# DimmerRGB_RevB.net
KiCad netlist of a schematic drawn in EAGLE
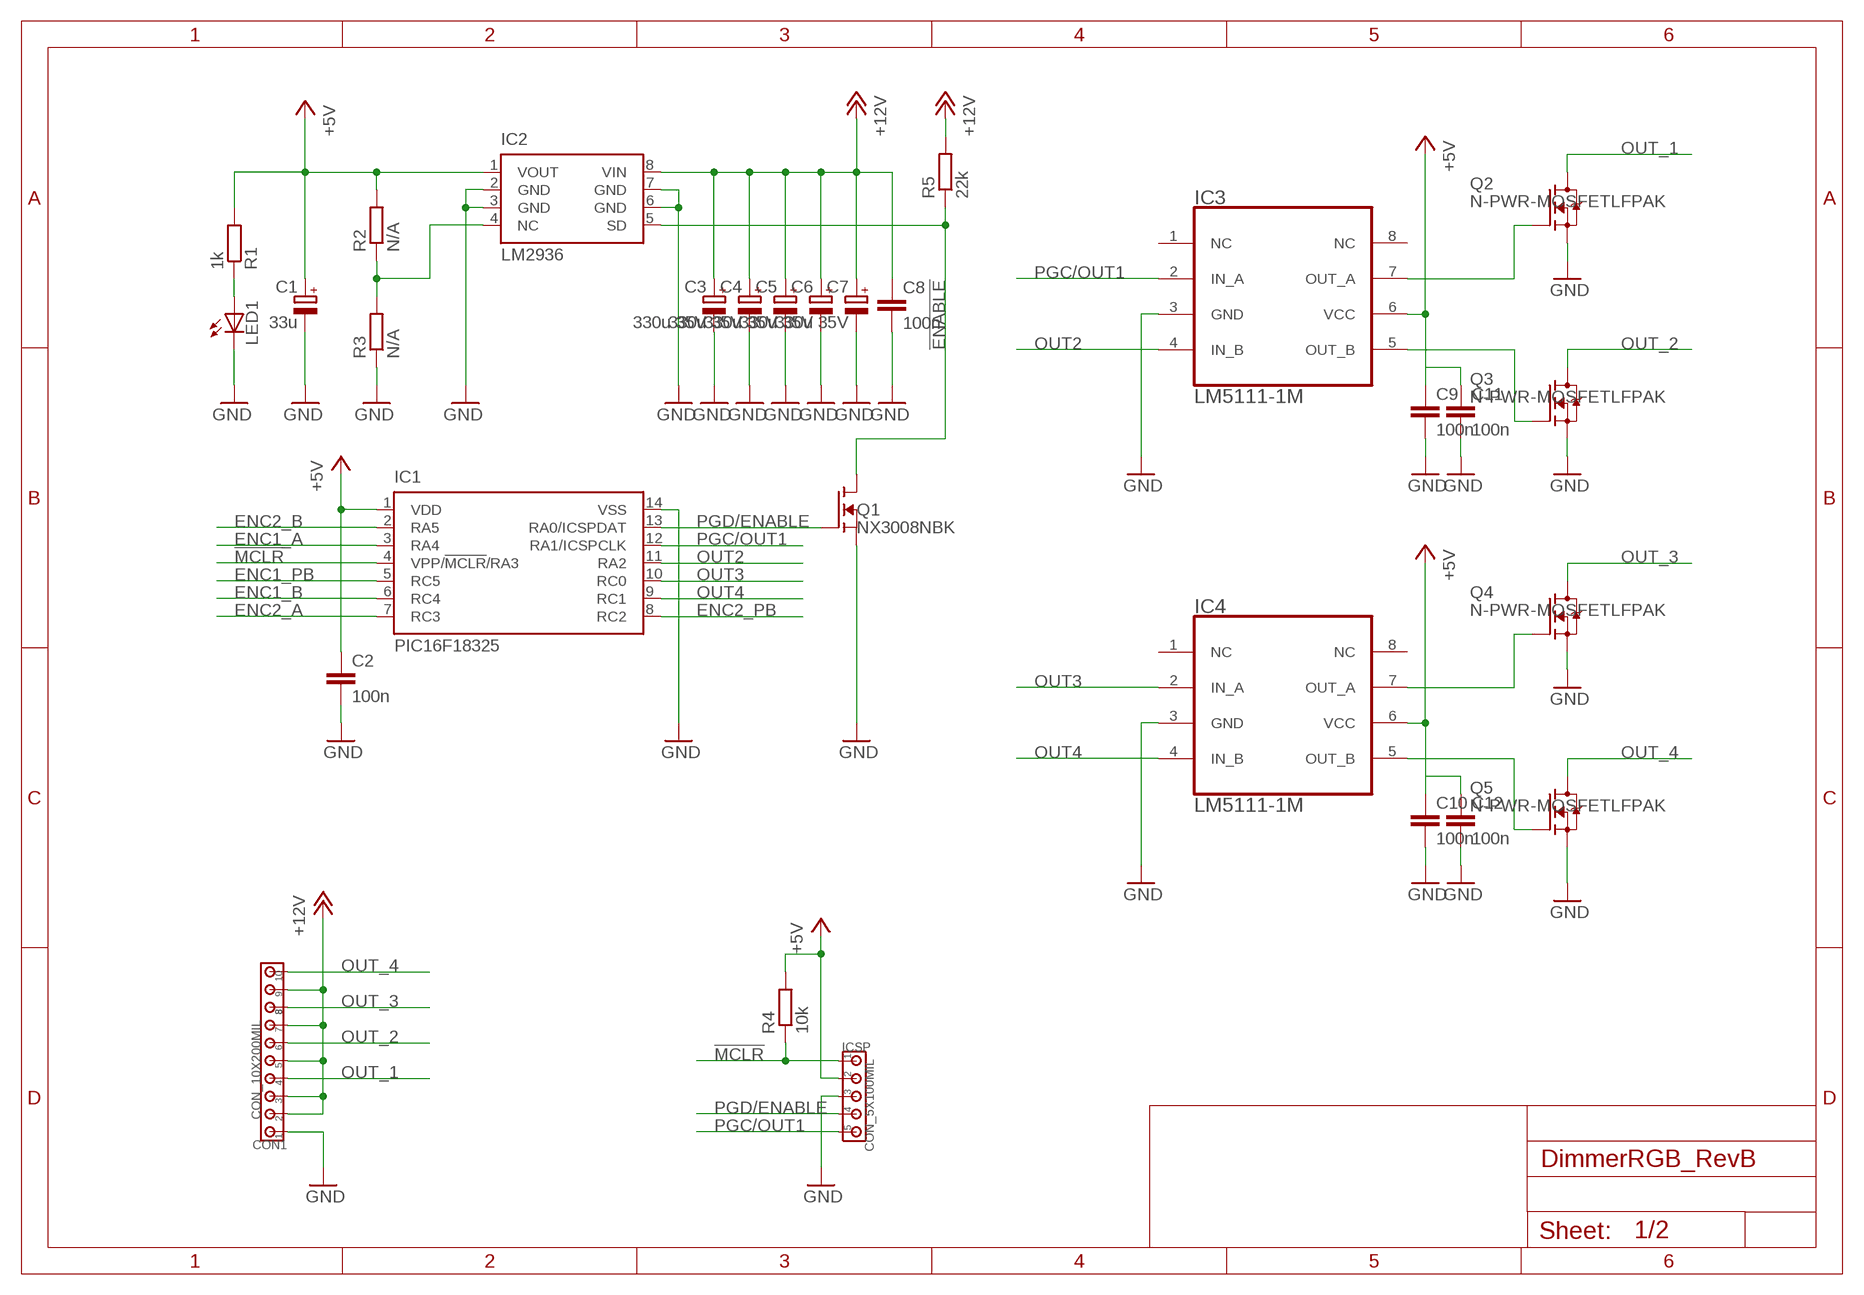
[diagram p0: schematic, sheet 1]
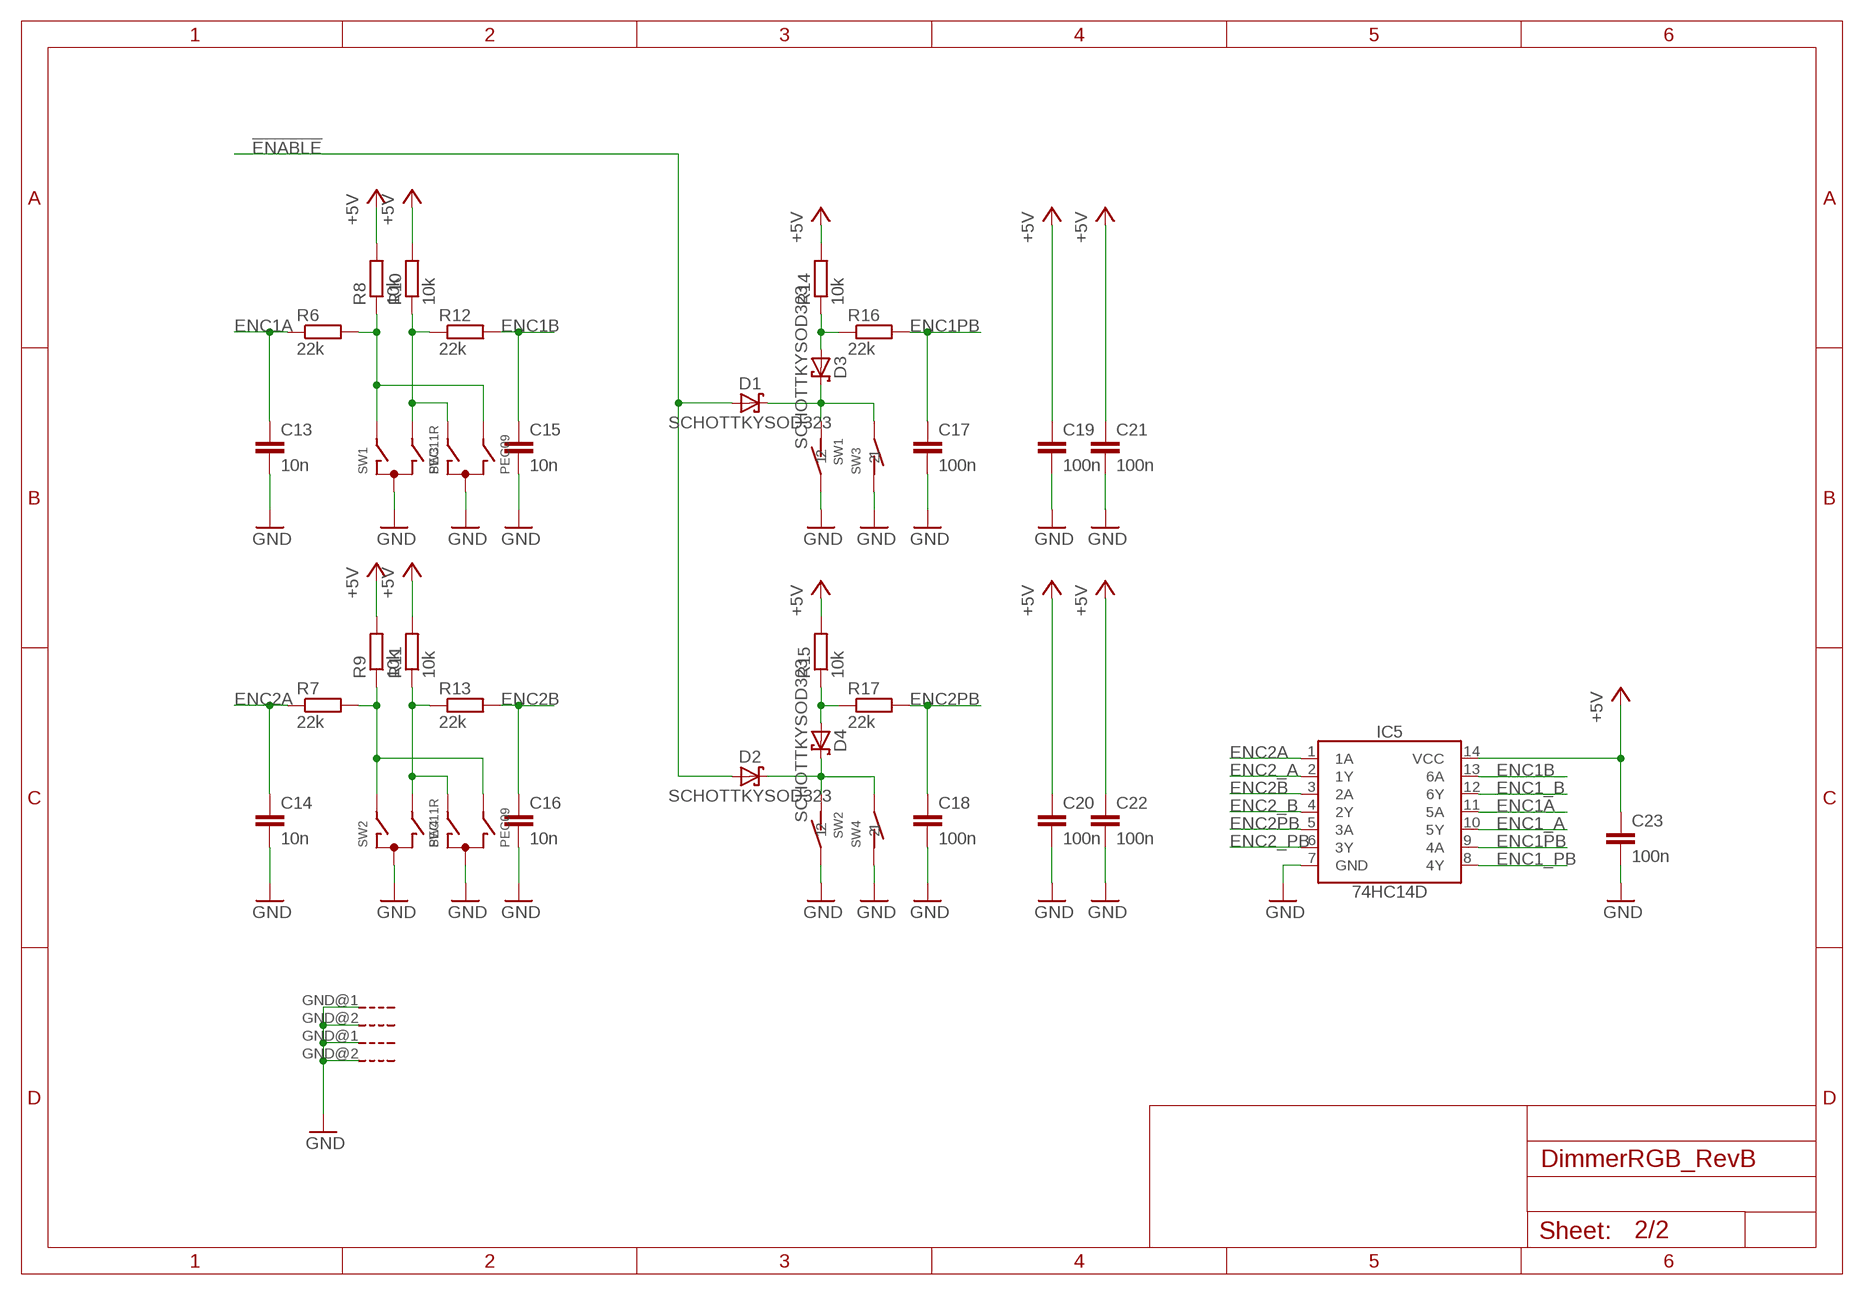
[diagram p1: schematic, sheet 2]

(export (version "E")
  (design (tool "Eeschema 10.0.6"))
  (components
    (comp (ref "C1")
      (value "33u")
      (footprint "eagle-import:SMC_C")
      (libsource (lib "eagle-import") (part "C_POLARIZEDSMC_C"))
    )
    (comp (ref "C2")
      (value "100n")
      (footprint "eagle-import:C0805")
      (libsource (lib "eagle-import") (part "CC0805"))
    )
    (comp (ref "C3")
      (value "330u 35V")
      (footprint "eagle-import:10MM")
      (libsource (lib "eagle-import") (part "C_POLARIZED10MM"))
    )
    (comp (ref "C4")
      (value "330u 35V")
      (footprint "eagle-import:10MM")
      (libsource (lib "eagle-import") (part "C_POLARIZED10MM"))
    )
    (comp (ref "C5")
      (value "330u 35V")
      (footprint "eagle-import:10MM")
      (libsource (lib "eagle-import") (part "C_POLARIZED10MM"))
    )
    (comp (ref "C6")
      (value "330u 35V")
      (footprint "eagle-import:10MM")
      (libsource (lib "eagle-import") (part "C_POLARIZED10MM"))
    )
    (comp (ref "C7")
      (value "330u 35V")
      (footprint "eagle-import:10MM")
      (libsource (lib "eagle-import") (part "C_POLARIZED10MM"))
    )
    (comp (ref "C8")
      (value "100n")
      (footprint "eagle-import:C0805")
      (libsource (lib "eagle-import") (part "CC0805"))
    )
    (comp (ref "C9")
      (value "100n")
      (footprint "eagle-import:C0805")
      (libsource (lib "eagle-import") (part "CC0805"))
    )
    (comp (ref "C10")
      (value "100n")
      (footprint "eagle-import:C0805")
      (libsource (lib "eagle-import") (part "CC0805"))
    )
    (comp (ref "C11")
      (value "100n")
      (footprint "eagle-import:C0805")
      (libsource (lib "eagle-import") (part "CC0805"))
    )
    (comp (ref "C12")
      (value "100n")
      (footprint "eagle-import:C0805")
      (libsource (lib "eagle-import") (part "CC0805"))
    )
    (comp (ref "CON1")
      (value "CON_10X200MIL")
      (footprint "eagle-import:200MIL_10X")
      (libsource (lib "eagle-import") (part "CON_10X200MIL"))
    )
    (comp (ref "IC1")
      (value "PIC16F18325")
      (footprint "eagle-import:SO14")
      (libsource (lib "eagle-import") (part "PIC16F18325"))
    )
    (comp (ref "IC2")
      (value "LM2936")
      (footprint "eagle-import:SOIC8")
      (libsource (lib "eagle-import") (part "LM2936"))
    )
    (comp (ref "IC3")
      (value "LM5111-1M")
      (footprint "eagle-import:SOIC8")
      (libsource (lib "eagle-import") (part "LM5111"))
    )
    (comp (ref "IC4")
      (value "LM5111-1M")
      (footprint "eagle-import:SOIC8")
      (libsource (lib "eagle-import") (part "LM5111"))
    )
    (comp (ref "ICSP")
      (value "CON_5X100MIL")
      (footprint "eagle-import:100MIL_5X")
      (libsource (lib "eagle-import") (part "CON_5X100MIL"))
    )
    (comp (ref "LED1")
      (value "LED0805")
      (footprint "eagle-import:LED0805")
      (libsource (lib "eagle-import") (part "LED0805"))
    )
    (comp (ref "Q1")
      (value "NX3008NBK")
      (footprint "eagle-import:SOT23")
      (libsource (lib "eagle-import") (part "N-FETSOT23"))
    )
    (comp (ref "Q2")
      (value "N-PWR-MOSFETLFPAK")
      (footprint "eagle-import:LFPAK")
      (libsource (lib "eagle-import") (part "N-PWR-MOSFETLFPAK"))
    )
    (comp (ref "Q3")
      (value "N-PWR-MOSFETLFPAK")
      (footprint "eagle-import:LFPAK")
      (libsource (lib "eagle-import") (part "N-PWR-MOSFETLFPAK"))
    )
    (comp (ref "Q4")
      (value "N-PWR-MOSFETLFPAK")
      (footprint "eagle-import:LFPAK")
      (libsource (lib "eagle-import") (part "N-PWR-MOSFETLFPAK"))
    )
    (comp (ref "Q5")
      (value "N-PWR-MOSFETLFPAK")
      (footprint "eagle-import:LFPAK")
      (libsource (lib "eagle-import") (part "N-PWR-MOSFETLFPAK"))
    )
    (comp (ref "R1")
      (value "1k")
      (footprint "eagle-import:R0805")
      (libsource (lib "eagle-import") (part "RESISTORR0805"))
    )
    (comp (ref "R2")
      (value "N/A")
      (footprint "eagle-import:R0805")
      (libsource (lib "eagle-import") (part "RESISTORR0805"))
    )
    (comp (ref "R3")
      (value "N/A")
      (footprint "eagle-import:R0805")
      (libsource (lib "eagle-import") (part "RESISTORR0805"))
    )
    (comp (ref "R4")
      (value "10k")
      (footprint "eagle-import:R0805")
      (libsource (lib "eagle-import") (part "RESISTORR0805"))
    )
    (comp (ref "R5")
      (value "22k")
      (footprint "eagle-import:R0805")
      (libsource (lib "eagle-import") (part "RESISTORR0805"))
    )
    (comp (ref "C13")
      (value "10n")
      (footprint "eagle-import:C0805")
      (libsource (lib "eagle-import") (part "CC0805"))
    )
    (comp (ref "C14")
      (value "10n")
      (footprint "eagle-import:C0805")
      (libsource (lib "eagle-import") (part "CC0805"))
    )
    (comp (ref "C15")
      (value "10n")
      (footprint "eagle-import:C0805")
      (libsource (lib "eagle-import") (part "CC0805"))
    )
    (comp (ref "C16")
      (value "10n")
      (footprint "eagle-import:C0805")
      (libsource (lib "eagle-import") (part "CC0805"))
    )
    (comp (ref "C17")
      (value "100n")
      (footprint "eagle-import:C0805")
      (libsource (lib "eagle-import") (part "CC0805"))
    )
    (comp (ref "C18")
      (value "100n")
      (footprint "eagle-import:C0805")
      (libsource (lib "eagle-import") (part "CC0805"))
    )
    (comp (ref "C19")
      (value "100n")
      (footprint "eagle-import:C0805")
      (libsource (lib "eagle-import") (part "CC0805"))
    )
    (comp (ref "C20")
      (value "100n")
      (footprint "eagle-import:C0805")
      (libsource (lib "eagle-import") (part "CC0805"))
    )
    (comp (ref "C21")
      (value "100n")
      (footprint "eagle-import:C0805")
      (libsource (lib "eagle-import") (part "CC0805"))
    )
    (comp (ref "C22")
      (value "100n")
      (footprint "eagle-import:C0805")
      (libsource (lib "eagle-import") (part "CC0805"))
    )
    (comp (ref "C23")
      (value "100n")
      (footprint "eagle-import:C0805")
      (libsource (lib "eagle-import") (part "CC0805"))
    )
    (comp (ref "D1")
      (value "SCHOTTKYSOD323")
      (footprint "eagle-import:SOD323")
      (libsource (lib "eagle-import") (part "SCHOTTKYSOD323"))
    )
    (comp (ref "D2")
      (value "SCHOTTKYSOD323")
      (footprint "eagle-import:SOD323")
      (libsource (lib "eagle-import") (part "SCHOTTKYSOD323"))
    )
    (comp (ref "D3")
      (value "SCHOTTKYSOD323")
      (footprint "eagle-import:SOD323")
      (libsource (lib "eagle-import") (part "SCHOTTKYSOD323"))
    )
    (comp (ref "D4")
      (value "SCHOTTKYSOD323")
      (footprint "eagle-import:SOD323")
      (libsource (lib "eagle-import") (part "SCHOTTKYSOD323"))
    )
    (comp (ref "IC5")
      (value "74HC14D")
      (footprint "eagle-import:SO14")
      (libsource (lib "eagle-import") (part "74HC14D"))
    )
    (comp (ref "R6")
      (value "22k")
      (footprint "eagle-import:R0805")
      (libsource (lib "eagle-import") (part "RESISTORR0805"))
    )
    (comp (ref "R7")
      (value "22k")
      (footprint "eagle-import:R0805")
      (libsource (lib "eagle-import") (part "RESISTORR0805"))
    )
    (comp (ref "R8")
      (value "10k")
      (footprint "eagle-import:R0805")
      (libsource (lib "eagle-import") (part "RESISTORR0805"))
    )
    (comp (ref "R9")
      (value "10k")
      (footprint "eagle-import:R0805")
      (libsource (lib "eagle-import") (part "RESISTORR0805"))
    )
    (comp (ref "R10")
      (value "10k")
      (footprint "eagle-import:R0805")
      (libsource (lib "eagle-import") (part "RESISTORR0805"))
    )
    (comp (ref "R11")
      (value "10k")
      (footprint "eagle-import:R0805")
      (libsource (lib "eagle-import") (part "RESISTORR0805"))
    )
    (comp (ref "R12")
      (value "22k")
      (footprint "eagle-import:R0805")
      (libsource (lib "eagle-import") (part "RESISTORR0805"))
    )
    (comp (ref "R13")
      (value "22k")
      (footprint "eagle-import:R0805")
      (libsource (lib "eagle-import") (part "RESISTORR0805"))
    )
    (comp (ref "R14")
      (value "10k")
      (footprint "eagle-import:R0805")
      (libsource (lib "eagle-import") (part "RESISTORR0805"))
    )
    (comp (ref "R15")
      (value "10k")
      (footprint "eagle-import:R0805")
      (libsource (lib "eagle-import") (part "RESISTORR0805"))
    )
    (comp (ref "R16")
      (value "22k")
      (footprint "eagle-import:R0805")
      (libsource (lib "eagle-import") (part "RESISTORR0805"))
    )
    (comp (ref "R17")
      (value "22k")
      (footprint "eagle-import:R0805")
      (libsource (lib "eagle-import") (part "RESISTORR0805"))
    )
    (comp (ref "SW1")
      (value "PEC11R")
      (footprint "eagle-import:ENCODER_BOURNS")
      (libsource (lib "eagle-import") (part "ENCODER_BOURNS"))
    )
    (comp (ref "SW2")
      (value "PEC11R")
      (footprint "eagle-import:ENCODER_BOURNS")
      (libsource (lib "eagle-import") (part "ENCODER_BOURNS"))
    )
    (comp (ref "SW3")
      (value "PEC09")
      (footprint "eagle-import:PEC09")
      (libsource (lib "eagle-import") (part "PEC09"))
    )
    (comp (ref "SW4")
      (value "PEC09")
      (footprint "eagle-import:PEC09")
      (libsource (lib "eagle-import") (part "PEC09"))
    )
  )
  (nets
    (net (code "1") (name "+5V") (class "Default")
      (node (ref "C1") (pin "+") (pinfunction "+_+") (pintype "passive"))
      (node (ref "C10") (pin "1") (pinfunction "1_1") (pintype "passive"))
      (node (ref "C11") (pin "1") (pinfunction "1_1") (pintype "passive"))
      (node (ref "C12") (pin "1") (pinfunction "1_1") (pintype "passive"))
      (node (ref "C19") (pin "1") (pinfunction "1_1") (pintype "passive"))
      (node (ref "C2") (pin "1") (pinfunction "1_1") (pintype "passive"))
      (node (ref "C20") (pin "1") (pinfunction "1_1") (pintype "passive"))
      (node (ref "C21") (pin "1") (pinfunction "1_1") (pintype "passive"))
      (node (ref "C22") (pin "1") (pinfunction "1_1") (pintype "passive"))
      (node (ref "C23") (pin "1") (pinfunction "1_1") (pintype "passive"))
      (node (ref "C9") (pin "1") (pinfunction "1_1") (pintype "passive"))
      (node (ref "IC1") (pin "1") (pinfunction "VDD_1") (pintype "power_in"))
      (node (ref "IC2") (pin "1") (pinfunction "VOUT_1") (pintype "output"))
      (node (ref "IC3") (pin "6") (pinfunction "VCC_6") (pintype "input"))
      (node (ref "IC4") (pin "6") (pinfunction "VCC_6") (pintype "input"))
      (node (ref "IC5") (pin "14") (pinfunction "VCC_14") (pintype "power_in"))
      (node (ref "ICSP") (pin "2") (pinfunction "2_2") (pintype "passive"))
      (node (ref "R1") (pin "2") (pinfunction "2_2") (pintype "passive"))
      (node (ref "R10") (pin "2") (pinfunction "2_2") (pintype "passive"))
      (node (ref "R11") (pin "2") (pinfunction "2_2") (pintype "passive"))
      (node (ref "R14") (pin "2") (pinfunction "2_2") (pintype "passive"))
      (node (ref "R15") (pin "2") (pinfunction "2_2") (pintype "passive"))
      (node (ref "R2") (pin "2") (pinfunction "2_2") (pintype "passive"))
      (node (ref "R4") (pin "2") (pinfunction "2_2") (pintype "passive"))
      (node (ref "R8") (pin "2") (pinfunction "2_2") (pintype "passive"))
      (node (ref "R9") (pin "2") (pinfunction "2_2") (pintype "passive"))
    )
    (net (code "2") (name "+12V") (class "Default")
      (node (ref "C3") (pin "+") (pinfunction "+_+") (pintype "passive"))
      (node (ref "C4") (pin "+") (pinfunction "+_+") (pintype "passive"))
      (node (ref "C5") (pin "+") (pinfunction "+_+") (pintype "passive"))
      (node (ref "C6") (pin "+") (pinfunction "+_+") (pintype "passive"))
      (node (ref "C7") (pin "+") (pinfunction "+_+") (pintype "passive"))
      (node (ref "C8") (pin "1") (pinfunction "1_1") (pintype "passive"))
      (node (ref "CON1") (pin "2") (pinfunction "P$2_2") (pintype "passive"))
      (node (ref "CON1") (pin "3") (pinfunction "P$3_3") (pintype "passive"))
      (node (ref "CON1") (pin "5") (pinfunction "P$5_5") (pintype "passive"))
      (node (ref "CON1") (pin "7") (pinfunction "P$7_7") (pintype "passive"))
      (node (ref "CON1") (pin "9") (pinfunction "P$9_9") (pintype "passive"))
      (node (ref "IC2") (pin "8") (pinfunction "VIN_8") (pintype "passive"))
      (node (ref "R5") (pin "2") (pinfunction "2_2") (pintype "passive"))
    )
    (net (code "3") (name "ENC1A") (class "Default")
      (node (ref "C13") (pin "1") (pinfunction "1_1") (pintype "passive"))
      (node (ref "IC5") (pin "11") (pinfunction "5A_11") (pintype "bidirectional"))
      (node (ref "R6") (pin "1") (pinfunction "1_1") (pintype "passive"))
    )
    (net (code "4") (name "ENC1B") (class "Default")
      (node (ref "C15") (pin "1") (pinfunction "1_1") (pintype "passive"))
      (node (ref "IC5") (pin "13") (pinfunction "6A_13") (pintype "bidirectional"))
      (node (ref "R12") (pin "2") (pinfunction "2_2") (pintype "passive"))
    )
    (net (code "5") (name "ENC1PB") (class "Default")
      (node (ref "C17") (pin "1") (pinfunction "1_1") (pintype "passive"))
      (node (ref "IC5") (pin "9") (pinfunction "4A_9") (pintype "bidirectional"))
      (node (ref "R16") (pin "2") (pinfunction "2_2") (pintype "passive"))
    )
    (net (code "6") (name "ENC1_A") (class "Default")
      (node (ref "IC1") (pin "3") (pinfunction "RA4_3") (pintype "bidirectional"))
      (node (ref "IC5") (pin "10") (pinfunction "5Y_10") (pintype "bidirectional"))
    )
    (net (code "7") (name "ENC1_B") (class "Default")
      (node (ref "IC1") (pin "6") (pinfunction "RC4_6") (pintype "bidirectional"))
      (node (ref "IC5") (pin "12") (pinfunction "6Y_12") (pintype "bidirectional"))
    )
    (net (code "8") (name "ENC1_PB") (class "Default")
      (node (ref "IC1") (pin "5") (pinfunction "RC5_5") (pintype "bidirectional"))
      (node (ref "IC5") (pin "8") (pinfunction "4Y_8") (pintype "bidirectional"))
    )
    (net (code "9") (name "ENC2A") (class "Default")
      (node (ref "C14") (pin "1") (pinfunction "1_1") (pintype "passive"))
      (node (ref "IC5") (pin "1") (pinfunction "1A_1") (pintype "input"))
      (node (ref "R7") (pin "1") (pinfunction "1_1") (pintype "passive"))
    )
    (net (code "10") (name "ENC2B") (class "Default")
      (node (ref "C16") (pin "1") (pinfunction "1_1") (pintype "passive"))
      (node (ref "IC5") (pin "3") (pinfunction "2A_3") (pintype "input"))
      (node (ref "R13") (pin "2") (pinfunction "2_2") (pintype "passive"))
    )
    (net (code "11") (name "ENC2PB") (class "Default")
      (node (ref "C18") (pin "1") (pinfunction "1_1") (pintype "passive"))
      (node (ref "IC5") (pin "5") (pinfunction "3A_5") (pintype "input"))
      (node (ref "R17") (pin "2") (pinfunction "2_2") (pintype "passive"))
    )
    (net (code "12") (name "ENC2_A") (class "Default")
      (node (ref "IC1") (pin "7") (pinfunction "RC3_7") (pintype "bidirectional"))
      (node (ref "IC5") (pin "2") (pinfunction "1Y_2") (pintype "input"))
    )
    (net (code "13") (name "ENC2_B") (class "Default")
      (node (ref "IC1") (pin "2") (pinfunction "RA5_2") (pintype "input"))
      (node (ref "IC5") (pin "4") (pinfunction "2Y_4") (pintype "input"))
    )
    (net (code "14") (name "ENC2_PB") (class "Default")
      (node (ref "IC1") (pin "8") (pinfunction "RC2_8") (pintype "bidirectional"))
      (node (ref "IC5") (pin "6") (pinfunction "3Y_6") (pintype "input"))
    )
    (net (code "15") (name "GND") (class "Default")
      (node (ref "C1") (pin "-") (pinfunction "-_-") (pintype "passive"))
      (node (ref "C10") (pin "2") (pinfunction "2_2") (pintype "passive"))
      (node (ref "C11") (pin "2") (pinfunction "2_2") (pintype "passive"))
      (node (ref "C12") (pin "2") (pinfunction "2_2") (pintype "passive"))
      (node (ref "C13") (pin "2") (pinfunction "2_2") (pintype "passive"))
      (node (ref "C14") (pin "2") (pinfunction "2_2") (pintype "passive"))
      (node (ref "C15") (pin "2") (pinfunction "2_2") (pintype "passive"))
      (node (ref "C16") (pin "2") (pinfunction "2_2") (pintype "passive"))
      (node (ref "C17") (pin "2") (pinfunction "2_2") (pintype "passive"))
      (node (ref "C18") (pin "2") (pinfunction "2_2") (pintype "passive"))
      (node (ref "C19") (pin "2") (pinfunction "2_2") (pintype "passive"))
      (node (ref "C2") (pin "2") (pinfunction "2_2") (pintype "passive"))
      (node (ref "C20") (pin "2") (pinfunction "2_2") (pintype "passive"))
      (node (ref "C21") (pin "2") (pinfunction "2_2") (pintype "passive"))
      (node (ref "C22") (pin "2") (pinfunction "2_2") (pintype "passive"))
      (node (ref "C23") (pin "2") (pinfunction "2_2") (pintype "passive"))
      (node (ref "C3") (pin "-") (pinfunction "-_-") (pintype "passive"))
      (node (ref "C4") (pin "-") (pinfunction "-_-") (pintype "passive"))
      (node (ref "C5") (pin "-") (pinfunction "-_-") (pintype "passive"))
      (node (ref "C6") (pin "-") (pinfunction "-_-") (pintype "passive"))
      (node (ref "C7") (pin "-") (pinfunction "-_-") (pintype "passive"))
      (node (ref "C8") (pin "2") (pinfunction "2_2") (pintype "passive"))
      (node (ref "C9") (pin "2") (pinfunction "2_2") (pintype "passive"))
      (node (ref "CON1") (pin "1") (pinfunction "P$1_1") (pintype "passive"))
      (node (ref "IC1") (pin "14") (pinfunction "VSS_14") (pintype "power_in"))
      (node (ref "IC2") (pin "2") (pinfunction "GND_2") (pintype "passive"))
      (node (ref "IC2") (pin "3") (pinfunction "GND_3") (pintype "passive"))
      (node (ref "IC2") (pin "6") (pinfunction "GND_6") (pintype "output"))
      (node (ref "IC2") (pin "7") (pinfunction "GND_7") (pintype "output"))
      (node (ref "IC3") (pin "3") (pinfunction "GND_3") (pintype "input"))
      (node (ref "IC4") (pin "3") (pinfunction "GND_3") (pintype "input"))
      (node (ref "IC5") (pin "7") (pinfunction "GND_7") (pintype "bidirectional"))
      (node (ref "ICSP") (pin "3") (pinfunction "3_3") (pintype "passive"))
      (node (ref "LED1") (pin "C") (pinfunction "C_C") (pintype "passive"))
      (node (ref "Q1") (pin "2") (pinfunction "S_2") (pintype "passive"))
      (node (ref "Q2") (pin "1") (pinfunction "S_1") (pintype "passive"))
      (node (ref "Q2") (pin "2") (pinfunction "S_2") (pintype "passive"))
      (node (ref "Q2") (pin "3") (pinfunction "S_3") (pintype "passive"))
      (node (ref "Q3") (pin "1") (pinfunction "S_1") (pintype "passive"))
      (node (ref "Q3") (pin "2") (pinfunction "S_2") (pintype "passive"))
      (node (ref "Q3") (pin "3") (pinfunction "S_3") (pintype "passive"))
      (node (ref "Q4") (pin "1") (pinfunction "S_1") (pintype "passive"))
      (node (ref "Q4") (pin "2") (pinfunction "S_2") (pintype "passive"))
      (node (ref "Q4") (pin "3") (pinfunction "S_3") (pintype "passive"))
      (node (ref "Q5") (pin "1") (pinfunction "S_1") (pintype "passive"))
      (node (ref "Q5") (pin "2") (pinfunction "S_2") (pintype "passive"))
      (node (ref "Q5") (pin "3") (pinfunction "S_3") (pintype "passive"))
      (node (ref "R3") (pin "1") (pinfunction "1_1") (pintype "passive"))
      (node (ref "SW1") (pin "2") (pinfunction "2_2") (pintype "passive"))
      (node (ref "SW1") (pin "C") (pinfunction "C_C") (pintype "passive"))
      (node (ref "SW1") (pin "GND@1") (pinfunction "G_GND@1") (pintype "passive"))
      (node (ref "SW1") (pin "GND@2") (pinfunction "G_GND@2") (pintype "passive"))
      (node (ref "SW2") (pin "2") (pinfunction "2_2") (pintype "passive"))
      (node (ref "SW2") (pin "C") (pinfunction "C_C") (pintype "passive"))
      (node (ref "SW2") (pin "GND@1") (pinfunction "G_GND@1") (pintype "passive"))
      (node (ref "SW2") (pin "GND@2") (pinfunction "G_GND@2") (pintype "passive"))
      (node (ref "SW3") (pin "C") (pinfunction "C_C") (pintype "passive"))
      (node (ref "SW3") (pin "D") (pinfunction "1_D") (pintype "passive"))
      (node (ref "SW4") (pin "C") (pinfunction "C_C") (pintype "passive"))
      (node (ref "SW4") (pin "D") (pinfunction "1_D") (pintype "passive"))
    )
    (net (code "16") (name "Net-(D3-PadA)") (class "Default")
      (node (ref "D3") (pin "A") (pinfunction "A_A") (pintype "passive"))
      (node (ref "R14") (pin "1") (pinfunction "1_1") (pintype "passive"))
      (node (ref "R16") (pin "1") (pinfunction "1_1") (pintype "passive"))
    )
    (net (code "17") (name "Net-(D4-PadA)") (class "Default")
      (node (ref "D4") (pin "A") (pinfunction "A_A") (pintype "passive"))
      (node (ref "R15") (pin "1") (pinfunction "1_1") (pintype "passive"))
      (node (ref "R17") (pin "1") (pinfunction "1_1") (pintype "passive"))
    )
    (net (code "18") (name "Net-(IC2-NC)") (class "Default")
      (node (ref "IC2") (pin "4") (pinfunction "NC_4") (pintype "output"))
      (node (ref "R2") (pin "1") (pinfunction "1_1") (pintype "passive"))
      (node (ref "R3") (pin "2") (pinfunction "2_2") (pintype "passive"))
    )
    (net (code "19") (name "Net-(IC3-OUT_A)") (class "Default")
      (node (ref "IC3") (pin "7") (pinfunction "OUT_A_7") (pintype "input"))
      (node (ref "Q2") (pin "4") (pinfunction "G_4") (pintype "passive"))
    )
    (net (code "20") (name "Net-(IC3-OUT_B)") (class "Default")
      (node (ref "IC3") (pin "5") (pinfunction "OUT_B_5") (pintype "bidirectional"))
      (node (ref "Q3") (pin "4") (pinfunction "G_4") (pintype "passive"))
    )
    (net (code "21") (name "Net-(IC4-OUT_A)") (class "Default")
      (node (ref "IC4") (pin "7") (pinfunction "OUT_A_7") (pintype "input"))
      (node (ref "Q4") (pin "4") (pinfunction "G_4") (pintype "passive"))
    )
    (net (code "22") (name "Net-(IC4-OUT_B)") (class "Default")
      (node (ref "IC4") (pin "5") (pinfunction "OUT_B_5") (pintype "bidirectional"))
      (node (ref "Q5") (pin "4") (pinfunction "G_4") (pintype "passive"))
    )
    (net (code "23") (name "Net-(LED1-PadA)") (class "Default")
      (node (ref "LED1") (pin "A") (pinfunction "A_A") (pintype "passive"))
      (node (ref "R1") (pin "1") (pinfunction "1_1") (pintype "passive"))
    )
    (net (code "24") (name "Net-(R6-Pad2)") (class "Default")
      (node (ref "R6") (pin "2") (pinfunction "2_2") (pintype "passive"))
      (node (ref "R8") (pin "1") (pinfunction "1_1") (pintype "passive"))
      (node (ref "SW1") (pin "A") (pinfunction "A_A") (pintype "passive"))
      (node (ref "SW3") (pin "B") (pinfunction "B_B") (pintype "passive"))
    )
    (net (code "25") (name "Net-(R7-Pad2)") (class "Default")
      (node (ref "R7") (pin "2") (pinfunction "2_2") (pintype "passive"))
      (node (ref "R9") (pin "1") (pinfunction "1_1") (pintype "passive"))
      (node (ref "SW2") (pin "A") (pinfunction "A_A") (pintype "passive"))
      (node (ref "SW4") (pin "B") (pinfunction "B_B") (pintype "passive"))
    )
    (net (code "26") (name "Net-(R10-Pad1)") (class "Default")
      (node (ref "R10") (pin "1") (pinfunction "1_1") (pintype "passive"))
      (node (ref "R12") (pin "1") (pinfunction "1_1") (pintype "passive"))
      (node (ref "SW1") (pin "B") (pinfunction "B_B") (pintype "passive"))
      (node (ref "SW3") (pin "A") (pinfunction "A_A") (pintype "passive"))
    )
    (net (code "27") (name "Net-(R11-Pad1)") (class "Default")
      (node (ref "R11") (pin "1") (pinfunction "1_1") (pintype "passive"))
      (node (ref "R13") (pin "1") (pinfunction "1_1") (pintype "passive"))
      (node (ref "SW2") (pin "B") (pinfunction "B_B") (pintype "passive"))
      (node (ref "SW4") (pin "A") (pinfunction "A_A") (pintype "passive"))
    )
    (net (code "28") (name "Net-(SW3B-2)") (class "Default")
      (node (ref "D1") (pin "C") (pinfunction "C_C") (pintype "passive"))
      (node (ref "D3") (pin "C") (pinfunction "C_C") (pintype "passive"))
      (node (ref "SW1") (pin "1") (pinfunction "1_1") (pintype "passive"))
      (node (ref "SW3") (pin "E") (pinfunction "2_E") (pintype "passive"))
    )
    (net (code "29") (name "Net-(SW4B-2)") (class "Default")
      (node (ref "D2") (pin "C") (pinfunction "C_C") (pintype "passive"))
      (node (ref "D4") (pin "C") (pinfunction "C_C") (pintype "passive"))
      (node (ref "SW2") (pin "1") (pinfunction "1_1") (pintype "passive"))
      (node (ref "SW4") (pin "E") (pinfunction "2_E") (pintype "passive"))
    )
    (net (code "30") (name "OUT2") (class "Default")
      (node (ref "IC1") (pin "11") (pinfunction "RA2_11") (pintype "bidirectional"))
      (node (ref "IC3") (pin "4") (pinfunction "IN_B_4") (pintype "passive"))
    )
    (net (code "31") (name "OUT3") (class "Default")
      (node (ref "IC1") (pin "10") (pinfunction "RC0_10") (pintype "bidirectional"))
      (node (ref "IC4") (pin "2") (pinfunction "IN_A_2") (pintype "input"))
    )
    (net (code "32") (name "OUT4") (class "Default")
      (node (ref "IC1") (pin "9") (pinfunction "RC1_9") (pintype "bidirectional"))
      (node (ref "IC4") (pin "4") (pinfunction "IN_B_4") (pintype "passive"))
    )
    (net (code "33") (name "OUT_1") (class "Default")
      (node (ref "CON1") (pin "4") (pinfunction "P$4_4") (pintype "passive"))
      (node (ref "Q2") (pin "MB1") (pinfunction "D_MB1") (pintype "passive"))
      (node (ref "Q2") (pin "MB2") (pinfunction "D_MB2") (pintype "passive"))
      (node (ref "Q2") (pin "MB3") (pinfunction "D_MB3") (pintype "passive"))
      (node (ref "Q2") (pin "VIA1") (pinfunction "D_VIA1") (pintype "passive"))
      (node (ref "Q2") (pin "VIA2") (pinfunction "D_VIA2") (pintype "passive"))
      (node (ref "Q2") (pin "VIA3") (pinfunction "D_VIA3") (pintype "passive"))
      (node (ref "Q2") (pin "VIA4") (pinfunction "D_VIA4") (pintype "passive"))
      (node (ref "Q2") (pin "VIA5") (pinfunction "D_VIA5") (pintype "passive"))
      (node (ref "Q2") (pin "VIA6") (pinfunction "D_VIA6") (pintype "passive"))
      (node (ref "Q2") (pin "VIA7") (pinfunction "D_VIA7") (pintype "passive"))
      (node (ref "Q2") (pin "VIA8") (pinfunction "D_VIA8") (pintype "passive"))
      (node (ref "Q2") (pin "VIA9") (pinfunction "D_VIA9") (pintype "passive"))
    )
    (net (code "34") (name "OUT_2") (class "Default")
      (node (ref "CON1") (pin "6") (pinfunction "P$6_6") (pintype "passive"))
      (node (ref "Q3") (pin "MB1") (pinfunction "D_MB1") (pintype "passive"))
      (node (ref "Q3") (pin "MB2") (pinfunction "D_MB2") (pintype "passive"))
      (node (ref "Q3") (pin "MB3") (pinfunction "D_MB3") (pintype "passive"))
      (node (ref "Q3") (pin "VIA1") (pinfunction "D_VIA1") (pintype "passive"))
      (node (ref "Q3") (pin "VIA2") (pinfunction "D_VIA2") (pintype "passive"))
      (node (ref "Q3") (pin "VIA3") (pinfunction "D_VIA3") (pintype "passive"))
      (node (ref "Q3") (pin "VIA4") (pinfunction "D_VIA4") (pintype "passive"))
      (node (ref "Q3") (pin "VIA5") (pinfunction "D_VIA5") (pintype "passive"))
      (node (ref "Q3") (pin "VIA6") (pinfunction "D_VIA6") (pintype "passive"))
      (node (ref "Q3") (pin "VIA7") (pinfunction "D_VIA7") (pintype "passive"))
      (node (ref "Q3") (pin "VIA8") (pinfunction "D_VIA8") (pintype "passive"))
      (node (ref "Q3") (pin "VIA9") (pinfunction "D_VIA9") (pintype "passive"))
    )
    (net (code "35") (name "OUT_3") (class "Default")
      (node (ref "CON1") (pin "8") (pinfunction "P$8_8") (pintype "passive"))
      (node (ref "Q4") (pin "MB1") (pinfunction "D_MB1") (pintype "passive"))
      (node (ref "Q4") (pin "MB2") (pinfunction "D_MB2") (pintype "passive"))
      (node (ref "Q4") (pin "MB3") (pinfunction "D_MB3") (pintype "passive"))
      (node (ref "Q4") (pin "VIA1") (pinfunction "D_VIA1") (pintype "passive"))
      (node (ref "Q4") (pin "VIA2") (pinfunction "D_VIA2") (pintype "passive"))
      (node (ref "Q4") (pin "VIA3") (pinfunction "D_VIA3") (pintype "passive"))
      (node (ref "Q4") (pin "VIA4") (pinfunction "D_VIA4") (pintype "passive"))
      (node (ref "Q4") (pin "VIA5") (pinfunction "D_VIA5") (pintype "passive"))
      (node (ref "Q4") (pin "VIA6") (pinfunction "D_VIA6") (pintype "passive"))
      (node (ref "Q4") (pin "VIA7") (pinfunction "D_VIA7") (pintype "passive"))
      (node (ref "Q4") (pin "VIA8") (pinfunction "D_VIA8") (pintype "passive"))
      (node (ref "Q4") (pin "VIA9") (pinfunction "D_VIA9") (pintype "passive"))
    )
    (net (code "36") (name "OUT_4") (class "Default")
      (node (ref "CON1") (pin "10") (pinfunction "P$10_10") (pintype "passive"))
      (node (ref "Q5") (pin "MB1") (pinfunction "D_MB1") (pintype "passive"))
      (node (ref "Q5") (pin "MB2") (pinfunction "D_MB2") (pintype "passive"))
      (node (ref "Q5") (pin "MB3") (pinfunction "D_MB3") (pintype "passive"))
      (node (ref "Q5") (pin "VIA1") (pinfunction "D_VIA1") (pintype "passive"))
      (node (ref "Q5") (pin "VIA2") (pinfunction "D_VIA2") (pintype "passive"))
      (node (ref "Q5") (pin "VIA3") (pinfunction "D_VIA3") (pintype "passive"))
      (node (ref "Q5") (pin "VIA4") (pinfunction "D_VIA4") (pintype "passive"))
      (node (ref "Q5") (pin "VIA5") (pinfunction "D_VIA5") (pintype "passive"))
      (node (ref "Q5") (pin "VIA6") (pinfunction "D_VIA6") (pintype "passive"))
      (node (ref "Q5") (pin "VIA7") (pinfunction "D_VIA7") (pintype "passive"))
      (node (ref "Q5") (pin "VIA8") (pinfunction "D_VIA8") (pintype "passive"))
      (node (ref "Q5") (pin "VIA9") (pinfunction "D_VIA9") (pintype "passive"))
    )
    (net (code "37") (name "PGC{slash}OUT1") (class "Default")
      (node (ref "IC1") (pin "12") (pinfunction "RA1/ICSPCLK_12") (pintype "bidirectional"))
      (node (ref "IC3") (pin "2") (pinfunction "IN_A_2") (pintype "input"))
      (node (ref "ICSP") (pin "5") (pinfunction "5_5") (pintype "passive"))
    )
    (net (code "38") (name "PGD{slash}ENABLE") (class "Default")
      (node (ref "IC1") (pin "13") (pinfunction "RA0/ICSPDAT_13") (pintype "bidirectional"))
      (node (ref "ICSP") (pin "4") (pinfunction "4_4") (pintype "passive"))
      (node (ref "Q1") (pin "1") (pinfunction "G_1") (pintype "passive"))
    )
    (net (code "39") (name "unconnected-(IC3-NC-Pad1)") (class "Default")
      (node (ref "IC3") (pin "1") (pinfunction "NC_1") (pintype "no_connect"))
    )
    (net (code "40") (name "unconnected-(IC3-NC-Pad8)") (class "Default")
      (node (ref "IC3") (pin "8") (pinfunction "NC_8") (pintype "no_connect"))
    )
    (net (code "41") (name "unconnected-(IC4-NC-Pad1)") (class "Default")
      (node (ref "IC4") (pin "1") (pinfunction "NC_1") (pintype "no_connect"))
    )
    (net (code "42") (name "unconnected-(IC4-NC-Pad8)") (class "Default")
      (node (ref "IC4") (pin "8") (pinfunction "NC_8") (pintype "no_connect"))
    )
    (net (code "43") (name "~{ENABLE}") (class "Default")
      (node (ref "D1") (pin "A") (pinfunction "A_A") (pintype "passive"))
      (node (ref "D2") (pin "A") (pinfunction "A_A") (pintype "passive"))
      (node (ref "IC2") (pin "5") (pinfunction "SD_5") (pintype "passive"))
      (node (ref "Q1") (pin "3") (pinfunction "D_3") (pintype "passive"))
      (node (ref "R5") (pin "1") (pinfunction "1_1") (pintype "passive"))
    )
    (net (code "44") (name "~{MCLR}") (class "Default")
      (node (ref "IC1") (pin "4") (pinfunction "VPP/~{MCLR}/RA3_4") (pintype "bidirectional"))
      (node (ref "ICSP") (pin "1") (pinfunction "1_1") (pintype "passive"))
      (node (ref "R4") (pin "1") (pinfunction "1_1") (pintype "passive"))
    )
  )
)
